# SMPS_5V.net
KiCad netlist of a schematic drawn in Altium Designer
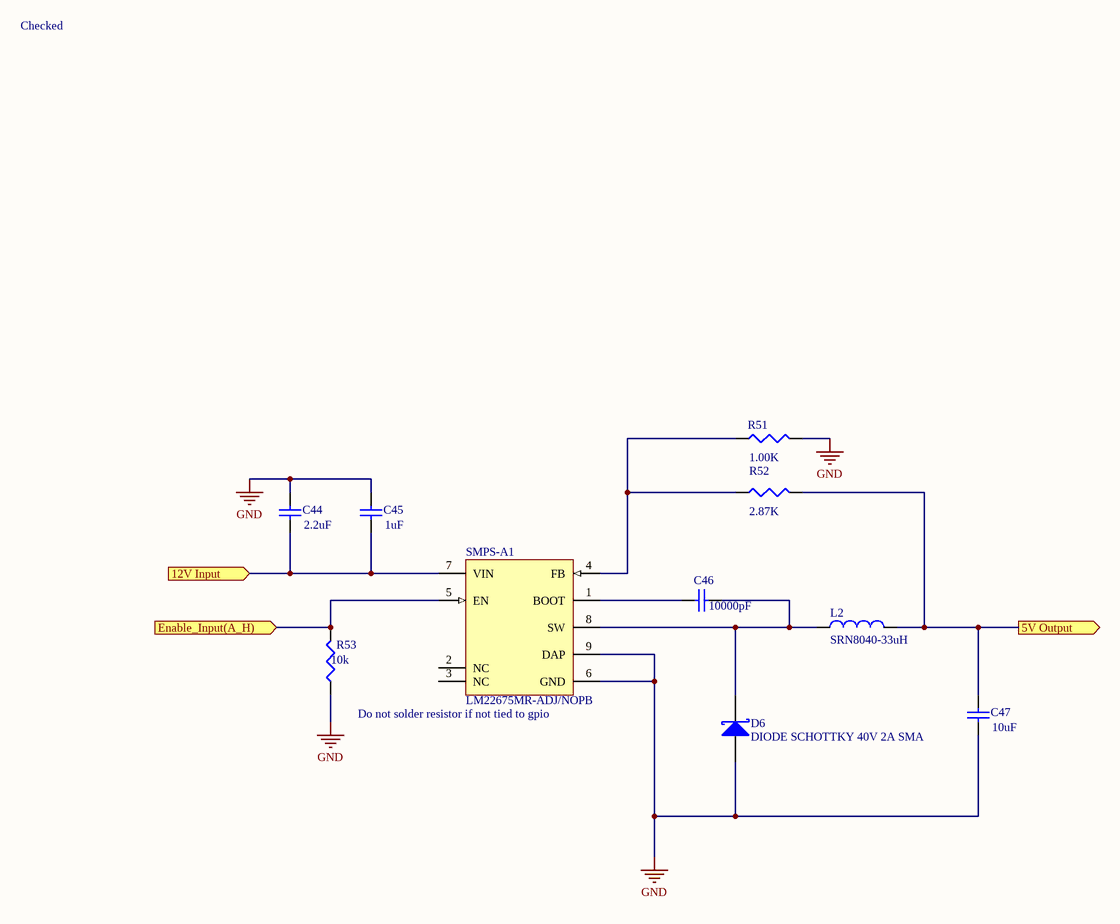
[diagram p0: SMPS_5V_.SchDoc]

(export (version "E")
  (design (tool "Eeschema 10.0.6"))
  (components
    (comp (ref "C44")
      (value "2.2uF")
      (footprint "Miscellaneous Devices:C1210")
      (description "Capacitor")
      (fields (field (name "Comment") "Cap-100V") (field (name "PUBLISHER") "Altium Limited"))
      (libsource (lib "Miscellaneous Devices") (part "Cap"))
    )
    (comp (ref "C45")
      (value "1uF")
      (footprint "CAPC2012X09M")
      (description "CAP CER 1uF 16v X7R 0805")
      (fields (field (name "TOLERANCE") "±10%") (field (name "MPN") "C0805C105K4RACTU"))
      (libsource (lib "esd_library") (part "CAP-X7R-1uF-16V-±10%"))
    )
    (comp (ref "C46")
      (value "10000pF")
      (footprint "CAPC2012X09M")
      (description "CAP CER 10000pF 100v X7R 0805")
      (fields (field (name "TOLERANCE") "±10%") (field (name "MPN") "C0805C103K1RACTU"))
      (libsource (lib "esd_library") (part "CAP-X7R-10000pF-100V-±10%"))
    )
    (comp (ref "C47")
      (value "10uF")
      (footprint "Miscellaneous Devices:C1210")
      (description "Capacitor")
      (fields (field (name "Comment") "Cap-10v-A") (field (name "PUBLISHER") "Altium Limited"))
      (libsource (lib "Miscellaneous Devices") (part "Cap"))
    )
    (comp (ref "D6")
      (value "DIODE SCHOTTKY 40V 2A SMA")
      (footprint "DIOM4326X23M")
      (description "Schottky Rectifier")
      (fields (field (name "MPN") "B240A-13-F"))
      (libsource (lib "esd_library") (part "DIODE SCHOTTKY 40V 2A SMA"))
    )
    (comp (ref "L2")
      (value "SRN8040-33uH")
      (footprint "INDP8080X40M")
      (description "FIXED IND 22UH 2.2A 100 MOHM SMD")
      (fields (field (name "MPN") "SRN8040-220M"))
      (libsource (lib "esd_library") (part "SRN8040"))
    )
    (comp (ref "R51")
      (value "1.00K")
      (footprint "RESC2112X05M")
      (description "RES SMD 1.00K OHM 1% 1/8W 0805")
      (fields (field (name "MPN") "CRCW08051K00FKEA") (field (name "Comment") "RFb1"))
      (libsource (lib "esd_library") (part "Resistor_1.00K"))
    )
    (comp (ref "R52")
      (value "2.87K")
      (footprint "RESC2112X05M")
      (description "RES SMD 2.87K OHM 1% 1/8W 0805")
      (fields (field (name "MPN") "CRCW08052K87FKEA") (field (name "Comment") "Res3"))
      (libsource (lib "esd_library") (part "Resistor_2.87K"))
    )
    (comp (ref "R53")
      (value "10k")
      (footprint "RESC2112X05M")
      (description "RES SMD 2.87K OHM 1% 1/8W 0805")
      (fields (field (name "MPN") "CRCW08052K87FKEA") (field (name "Comment") "Res3"))
      (libsource (lib "esd_library") (part "Resistor_2.87K"))
    )
    (comp (ref "SMPS-A1")
      (value "LM22675MR-ADJ/NOPB")
      (footprint "MRA08B_L")
      (description "1A SIMPLE SWITCHER®, Step-Down Voltage Regulator with Precision Enable, 8-pin PSOP, Pb-Free")
      (fields
        (field (name "MANUFACTURER") "National Semiconductor")
        (field (name "MPN") "LM22675MRE-ADJ/NOPB")
      )
      (libsource (lib "esd_library") (part "LM22675MR-ADJ/NOPB"))
    )
  )
  (nets
    (net (code "1") (name "/5V Output") (class "Default")
      (node (ref "C47") (pin "2") (pinfunction "2_2") (pintype "passive"))
      (node (ref "L2") (pin "2") (pinfunction "2_2") (pintype "passive"))
      (node (ref "R52") (pin "2") (pinfunction "2_2") (pintype "passive"))
    )
    (net (code "2") (name "/12V Input") (class "Default")
      (node (ref "C44") (pin "1") (pinfunction "1_1") (pintype "passive"))
      (node (ref "C45") (pin "1") (pinfunction "1_1") (pintype "passive"))
      (node (ref "SMPS-A1") (pin "7") (pinfunction "VIN_7") (pintype "power_in"))
    )
    (net (code "3") (name "/Enable_Input(A_H)") (class "Default")
      (node (ref "R53") (pin "2") (pinfunction "2_2") (pintype "passive"))
      (node (ref "SMPS-A1") (pin "5") (pinfunction "EN_5") (pintype "input"))
    )
    (net (code "4") (name "GND") (class "Default")
      (node (ref "C44") (pin "2") (pinfunction "2_2") (pintype "passive"))
      (node (ref "C45") (pin "2") (pinfunction "2_2") (pintype "passive"))
      (node (ref "C47") (pin "1") (pinfunction "1_1") (pintype "passive"))
      (node (ref "D6") (pin "2") (pinfunction "A_2") (pintype "passive"))
      (node (ref "R51") (pin "2") (pinfunction "2_2") (pintype "passive"))
      (node (ref "R53") (pin "1") (pinfunction "1_1") (pintype "passive"))
      (node (ref "SMPS-A1") (pin "6") (pinfunction "GND_6") (pintype "power_in"))
      (node (ref "SMPS-A1") (pin "9") (pinfunction "DAP_9") (pintype "power_in"))
    )
    (net (code "5") (name "Net-(D6-K)") (class "Default")
      (node (ref "C46") (pin "1") (pinfunction "1_1") (pintype "passive"))
      (node (ref "D6") (pin "1") (pinfunction "K_1") (pintype "passive"))
      (node (ref "L2") (pin "1") (pinfunction "1_1") (pintype "passive"))
      (node (ref "SMPS-A1") (pin "8") (pinfunction "SW_8") (pintype "power_in"))
    )
    (net (code "6") (name "Net-(SMPS-A1-BOOT)") (class "Default")
      (node (ref "C46") (pin "2") (pinfunction "2_2") (pintype "passive"))
      (node (ref "SMPS-A1") (pin "1") (pinfunction "BOOT_1") (pintype "passive"))
    )
    (net (code "7") (name "Net-(SMPS-A1-FB)") (class "Default")
      (node (ref "R51") (pin "1") (pinfunction "1_1") (pintype "passive"))
      (node (ref "R52") (pin "1") (pinfunction "1_1") (pintype "passive"))
      (node (ref "SMPS-A1") (pin "4") (pinfunction "FB_4") (pintype "input"))
    )
    (net (code "8") (name "unconnected-(SMPS-A1-NC-Pad2)") (class "Default")
      (node (ref "SMPS-A1") (pin "2") (pinfunction "NC_2") (pintype "passive"))
    )
    (net (code "9") (name "unconnected-(SMPS-A1-NC-Pad3)") (class "Default")
      (node (ref "SMPS-A1") (pin "3") (pinfunction "NC_3") (pintype "passive"))
    )
  )
)
